# 8LEDs_thin.net
KiCad netlist of a schematic drawn in EAGLE
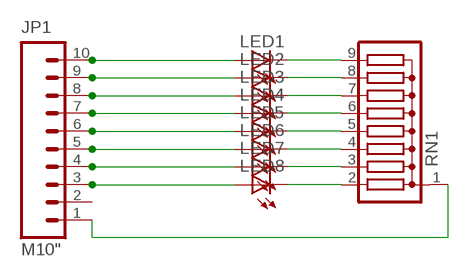
[diagram p0: schematic, sheet 1]

(export (version "E")
  (design (tool "Eeschema 10.0.6"))
  (components
    (comp (ref "JP1")
      (value "M10\"")
      (footprint "eagle-import:1X10LONGPAD")
      (libsource (lib "eagle-import") (part "M10{dblquote}"))
    )
    (comp (ref "LED1")
      (value "LED5MM")
      (footprint "eagle-import:LED5MM")
      (libsource (lib "eagle-import") (part "LED5MM"))
    )
    (comp (ref "LED2")
      (value "LED5MM")
      (footprint "eagle-import:LED5MM")
      (libsource (lib "eagle-import") (part "LED5MM"))
    )
    (comp (ref "LED3")
      (value "LED5MM")
      (footprint "eagle-import:LED5MM")
      (libsource (lib "eagle-import") (part "LED5MM"))
    )
    (comp (ref "LED4")
      (value "LED5MM")
      (footprint "eagle-import:LED5MM")
      (libsource (lib "eagle-import") (part "LED5MM"))
    )
    (comp (ref "LED5")
      (value "LED5MM")
      (footprint "eagle-import:LED5MM")
      (libsource (lib "eagle-import") (part "LED5MM"))
    )
    (comp (ref "LED6")
      (value "LED5MM")
      (footprint "eagle-import:LED5MM")
      (libsource (lib "eagle-import") (part "LED5MM"))
    )
    (comp (ref "LED7")
      (value "LED5MM")
      (footprint "eagle-import:LED5MM")
      (libsource (lib "eagle-import") (part "LED5MM"))
    )
    (comp (ref "LED8")
      (value "LED5MM")
      (footprint "eagle-import:LED5MM")
      (libsource (lib "eagle-import") (part "LED5MM"))
    )
    (comp (ref "RN1")
      (value "G08R")
      (footprint "eagle-import:SIL9")
      (libsource (lib "eagle-import") (part "G08R"))
    )
  )
  (nets
    (net (code "1") (name "Net-(JP1-Pad1)") (class "Default")
      (node (ref "JP1") (pin "1") (pinfunction "1_1") (pintype "passive"))
      (node (ref "RN1") (pin "1") (pinfunction "1_1") (pintype "passive"))
    )
    (net (code "2") (name "Net-(JP1-Pad3)") (class "Default")
      (node (ref "JP1") (pin "3") (pinfunction "3_3") (pintype "passive"))
      (node (ref "LED8") (pin "A") (pinfunction "A_A") (pintype "passive"))
    )
    (net (code "3") (name "Net-(JP1-Pad4)") (class "Default")
      (node (ref "JP1") (pin "4") (pinfunction "4_4") (pintype "passive"))
      (node (ref "LED7") (pin "A") (pinfunction "A_A") (pintype "passive"))
    )
    (net (code "4") (name "Net-(JP1-Pad5)") (class "Default")
      (node (ref "JP1") (pin "5") (pinfunction "5_5") (pintype "passive"))
      (node (ref "LED6") (pin "A") (pinfunction "A_A") (pintype "passive"))
    )
    (net (code "5") (name "Net-(JP1-Pad6)") (class "Default")
      (node (ref "JP1") (pin "6") (pinfunction "6_6") (pintype "passive"))
      (node (ref "LED5") (pin "A") (pinfunction "A_A") (pintype "passive"))
    )
    (net (code "6") (name "Net-(JP1-Pad7)") (class "Default")
      (node (ref "JP1") (pin "7") (pinfunction "7_7") (pintype "passive"))
      (node (ref "LED4") (pin "A") (pinfunction "A_A") (pintype "passive"))
    )
    (net (code "7") (name "Net-(JP1-Pad8)") (class "Default")
      (node (ref "JP1") (pin "8") (pinfunction "8_8") (pintype "passive"))
      (node (ref "LED3") (pin "A") (pinfunction "A_A") (pintype "passive"))
    )
    (net (code "8") (name "Net-(JP1-Pad9)") (class "Default")
      (node (ref "JP1") (pin "9") (pinfunction "9_9") (pintype "passive"))
      (node (ref "LED2") (pin "A") (pinfunction "A_A") (pintype "passive"))
    )
    (net (code "9") (name "Net-(JP1-Pad10)") (class "Default")
      (node (ref "JP1") (pin "10") (pinfunction "10_10") (pintype "passive"))
      (node (ref "LED1") (pin "A") (pinfunction "A_A") (pintype "passive"))
    )
    (net (code "10") (name "Net-(LED1-C)") (class "Default")
      (node (ref "LED1") (pin "K") (pinfunction "C_K") (pintype "passive"))
      (node (ref "RN1") (pin "9") (pinfunction "9_9") (pintype "passive"))
    )
    (net (code "11") (name "Net-(LED2-C)") (class "Default")
      (node (ref "LED2") (pin "K") (pinfunction "C_K") (pintype "passive"))
      (node (ref "RN1") (pin "8") (pinfunction "8_8") (pintype "passive"))
    )
    (net (code "12") (name "Net-(LED3-C)") (class "Default")
      (node (ref "LED3") (pin "K") (pinfunction "C_K") (pintype "passive"))
      (node (ref "RN1") (pin "7") (pinfunction "7_7") (pintype "passive"))
    )
    (net (code "13") (name "Net-(LED4-C)") (class "Default")
      (node (ref "LED4") (pin "K") (pinfunction "C_K") (pintype "passive"))
      (node (ref "RN1") (pin "6") (pinfunction "6_6") (pintype "passive"))
    )
    (net (code "14") (name "Net-(LED5-C)") (class "Default")
      (node (ref "LED5") (pin "K") (pinfunction "C_K") (pintype "passive"))
      (node (ref "RN1") (pin "5") (pinfunction "5_5") (pintype "passive"))
    )
    (net (code "15") (name "Net-(LED6-C)") (class "Default")
      (node (ref "LED6") (pin "K") (pinfunction "C_K") (pintype "passive"))
      (node (ref "RN1") (pin "4") (pinfunction "4_4") (pintype "passive"))
    )
    (net (code "16") (name "Net-(LED7-C)") (class "Default")
      (node (ref "LED7") (pin "K") (pinfunction "C_K") (pintype "passive"))
      (node (ref "RN1") (pin "3") (pinfunction "3_3") (pintype "passive"))
    )
    (net (code "17") (name "Net-(LED8-C)") (class "Default")
      (node (ref "LED8") (pin "K") (pinfunction "C_K") (pintype "passive"))
      (node (ref "RN1") (pin "2") (pinfunction "2_2") (pintype "passive"))
    )
    (net (code "18") (name "unconnected-(JP1-Pad2)") (class "Default")
      (node (ref "JP1") (pin "2") (pinfunction "2_2") (pintype "passive"))
    )
  )
)
